# ProDoc_Schematic_Edge_Nexus_2026-03-18.net
KiCad netlist of a schematic drawn in EasyEDA Pro
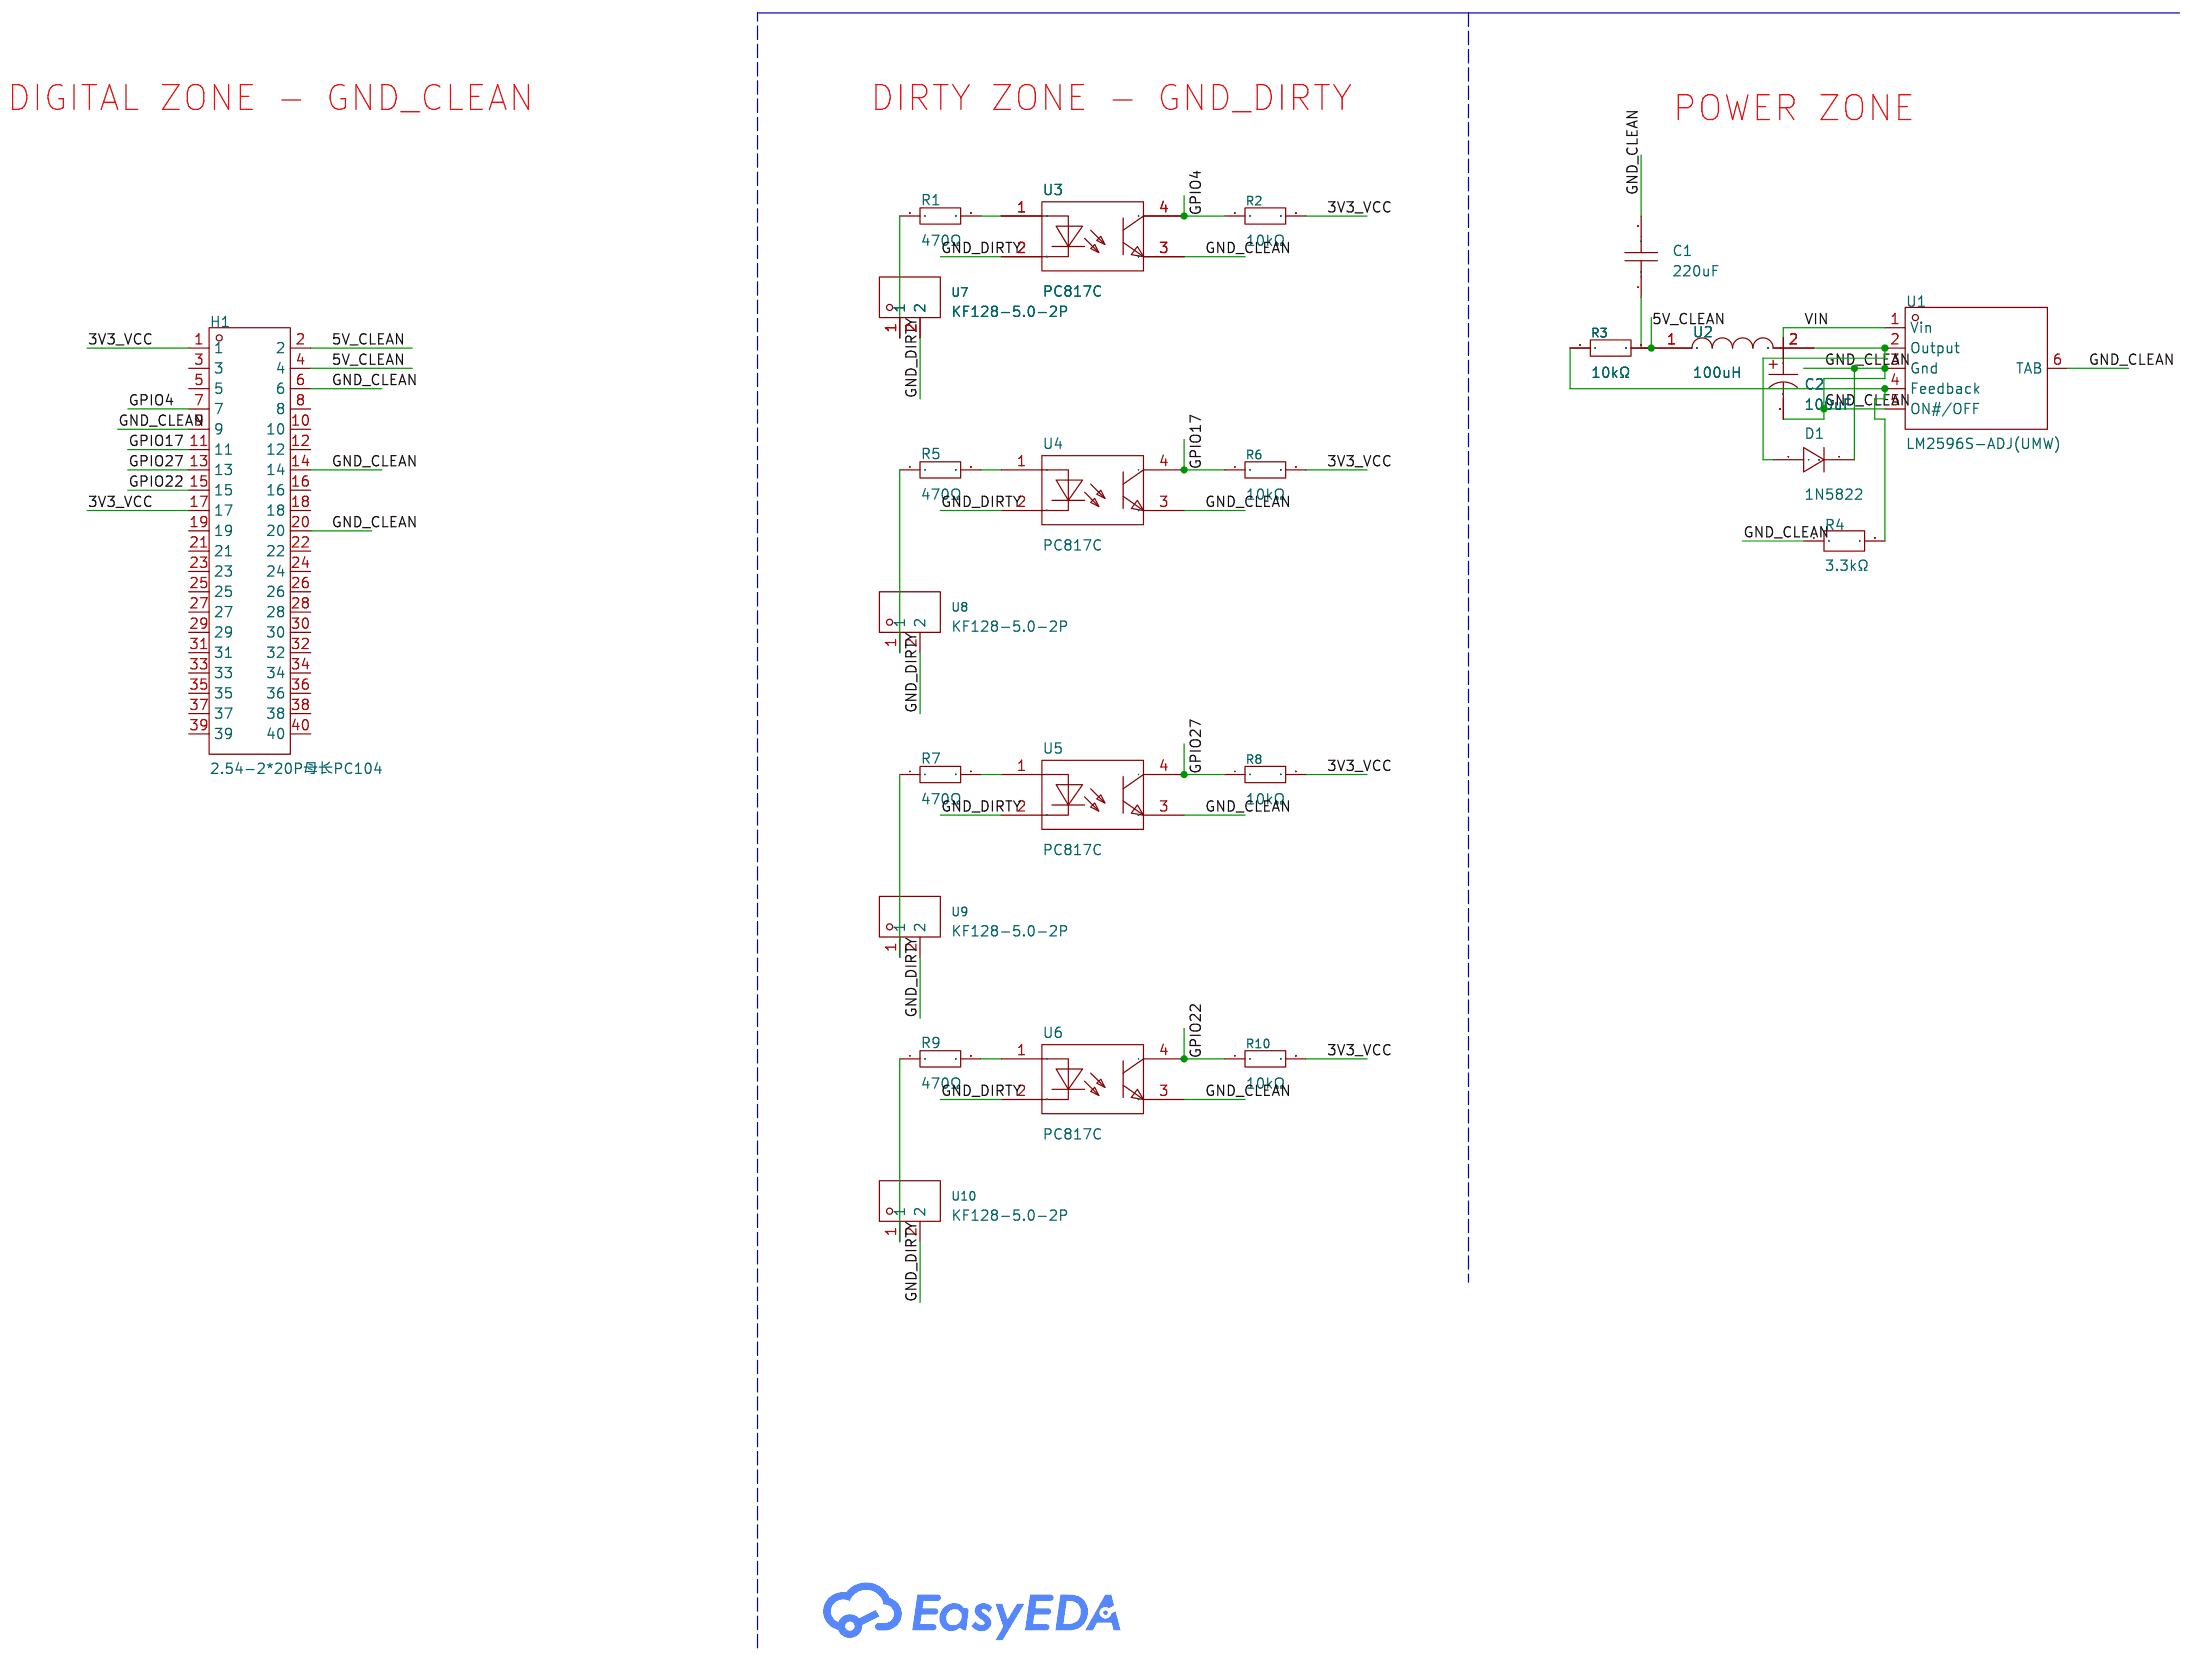
[diagram p0: schematic sheet]

(export (version "E")
  (design (tool "Eeschema 10.0.6"))
  (components
    (comp (ref "C1")
      (value "220uF")
      (footprint "easyedapro:C1210")
      (description "Capacitance:220uF Tolerance:±20% Tolerance:±20% Voltage Rating:6.3V Temperature Coefficient:X5R")
      (fields
        (field (name "Manufacturer Part") "CL32A227MQVNNNE")
        (field (name "Manufacturer") "SAMSUNG(三星)")
      )
      (libsource (lib "easyedapro") (part "CL32A227MQVNNNE"))
    )
    (comp (ref "C2")
      (value "100uF")
      (footprint "easyedapro:CAP-TH_BD8.0-P3.50-D0.6-FD-H10.0")
      (fields (field (name "Manufacturer Part") "100uF35V8x11GF") (field (name "Manufacturer") "Econd(米朗电子)"))
      (libsource (lib "easyedapro") (part "100UF35V8X11GF"))
    )
    (comp (ref "D1")
      (value "1N5822")
      (footprint "easyedapro:DO-201AD_BD5.3-L8.4-P12.50-D1.4-RD")
      (fields (field (name "Manufacturer") "LRC(乐山无线电)"))
      (libsource (lib "easyedapro") (part "1N5822_C82806"))
    )
    (comp (ref "H1")
      (value "2.54-2*20P母长PC104")
      (footprint "easyedapro:HDR-TH_40P-P2.54-V-F-R2-C20-S2.54-2")
      (fields (field (name "Manufacturer") "BOOMELE(博穆精密)"))
      (libsource (lib "easyedapro") (part "2.54mm 2*20P"))
    )
    (comp (ref "R1")
      (value "470Ω")
      (footprint "easyedapro:R0402")
      (fields (field (name "Manufacturer Part") "RC0402JR-07470RL") (field (name "Manufacturer") "YAGEO(国巨)"))
      (libsource (lib "easyedapro") (part "RC0402JR-07470RL"))
    )
    (comp (ref "R2")
      (value "10kΩ")
      (footprint "easyedapro:R0402")
      (fields
        (field (name "Manufacturer Part") "TR0402D10K0Q1025Z")
        (field (name "Manufacturer") "EVER OHMS(天二科技)")
      )
      (libsource (lib "easyedapro") (part "TR0402D10KQ1025"))
    )
    (comp (ref "R3")
      (value "10kΩ")
      (footprint "easyedapro:R0402")
      (fields
        (field (name "Manufacturer Part") "TR0402D10K0Q1025Z")
        (field (name "Manufacturer") "EVER OHMS(天二科技)")
      )
      (libsource (lib "easyedapro") (part "TR0402D10KQ1025"))
    )
    (comp (ref "R4")
      (value "3.3kΩ")
      (footprint "easyedapro:RES-TH_BD4.5-L11.5-P15.50-D0.8")
      (fields (field (name "Manufacturer Part") "MF1W-3.3KΩ±1%T") (field (name "Manufacturer") "华星机电"))
      (libsource (lib "easyedapro") (part "MF1W-3.3KΩ±1%T"))
    )
    (comp (ref "R5")
      (value "470Ω")
      (footprint "easyedapro:R0402")
      (fields (field (name "Manufacturer Part") "RC0402JR-07470RL") (field (name "Manufacturer") "YAGEO(国巨)"))
      (libsource (lib "easyedapro") (part "RC0402JR-07470RL"))
    )
    (comp (ref "R6")
      (value "10kΩ")
      (footprint "easyedapro:R0402")
      (fields
        (field (name "Manufacturer Part") "TR0402D10K0Q1025Z")
        (field (name "Manufacturer") "EVER OHMS(天二科技)")
      )
      (libsource (lib "easyedapro") (part "TR0402D10KQ1025"))
    )
    (comp (ref "R7")
      (value "470Ω")
      (footprint "easyedapro:R0402")
      (fields (field (name "Manufacturer Part") "RC0402JR-07470RL") (field (name "Manufacturer") "YAGEO(国巨)"))
      (libsource (lib "easyedapro") (part "RC0402JR-07470RL"))
    )
    (comp (ref "R8")
      (value "10kΩ")
      (footprint "easyedapro:R0402")
      (fields
        (field (name "Manufacturer Part") "TR0402D10K0Q1025Z")
        (field (name "Manufacturer") "EVER OHMS(天二科技)")
      )
      (libsource (lib "easyedapro") (part "TR0402D10KQ1025"))
    )
    (comp (ref "R9")
      (value "470Ω")
      (footprint "easyedapro:R0402")
      (fields (field (name "Manufacturer Part") "RC0402JR-07470RL") (field (name "Manufacturer") "YAGEO(国巨)"))
      (libsource (lib "easyedapro") (part "RC0402JR-07470RL"))
    )
    (comp (ref "R10")
      (value "10kΩ")
      (footprint "easyedapro:R0402")
      (fields
        (field (name "Manufacturer Part") "TR0402D10K0Q1025Z")
        (field (name "Manufacturer") "EVER OHMS(天二科技)")
      )
      (libsource (lib "easyedapro") (part "TR0402D10KQ1025"))
    )
    (comp (ref "U1")
      (value "LM2596S-ADJ(UMW)")
      (footprint "easyedapro:TO-263-5_L10.2-W8.9-P1.70-BR")
      (fields (field (name "Manufacturer") "UMW(友台半导体)"))
      (libsource (lib "easyedapro") (part "LM2596S-ADJ"))
    )
    (comp (ref "U2")
      (value "100uH")
      (footprint "easyedapro:IND-SMD_L12.3-W12.3")
      (fields (field (name "Manufacturer Part") "CYH127-100UH") (field (name "Manufacturer") "SHOU HAN(首韩)"))
      (libsource (lib "easyedapro") (part "CYH127-100UH"))
    )
    (comp (ref "U3")
      (value "PC817C")
      (footprint "easyedapro:OPTO-SMD-4_L4.6-W6.5-P2.54-LS10.3-TL")
      (fields (field (name "Manufacturer") "GOODWORK(固得沃克)"))
      (libsource (lib "easyedapro") (part "PC817C_C3025164"))
    )
    (comp (ref "U4")
      (value "PC817C")
      (footprint "easyedapro:OPTO-SMD-4_L4.6-W6.5-P2.54-LS10.3-TL")
      (fields (field (name "Manufacturer") "GOODWORK(固得沃克)"))
      (libsource (lib "easyedapro") (part "PC817C_C3025164"))
    )
    (comp (ref "U5")
      (value "PC817C")
      (footprint "easyedapro:OPTO-SMD-4_L4.6-W6.5-P2.54-LS10.3-TL")
      (fields (field (name "Manufacturer") "GOODWORK(固得沃克)"))
      (libsource (lib "easyedapro") (part "PC817C_C3025164"))
    )
    (comp (ref "U6")
      (value "PC817C")
      (footprint "easyedapro:OPTO-SMD-4_L4.6-W6.5-P2.54-LS10.3-TL")
      (fields (field (name "Manufacturer") "GOODWORK(固得沃克)"))
      (libsource (lib "easyedapro") (part "PC817C_C3025164"))
    )
    (comp (ref "U7")
      (value "KF128-5.0-2P")
      (footprint "easyedapro:CONN-TH_P5.00_KF128-5.0-2P")
      (fields (field (name "Manufacturer") "KEFA(科发)"))
      (libsource (lib "easyedapro") (part "KF128-5.0-2P"))
    )
    (comp (ref "U8")
      (value "KF128-5.0-2P")
      (footprint "easyedapro:CONN-TH_P5.00_KF128-5.0-2P")
      (fields (field (name "Manufacturer") "KEFA(科发)"))
      (libsource (lib "easyedapro") (part "KF128-5.0-2P"))
    )
    (comp (ref "U9")
      (value "KF128-5.0-2P")
      (footprint "easyedapro:CONN-TH_P5.00_KF128-5.0-2P")
      (fields (field (name "Manufacturer") "KEFA(科发)"))
      (libsource (lib "easyedapro") (part "KF128-5.0-2P"))
    )
    (comp (ref "U10")
      (value "KF128-5.0-2P")
      (footprint "easyedapro:CONN-TH_P5.00_KF128-5.0-2P")
      (fields (field (name "Manufacturer") "KEFA(科发)"))
      (libsource (lib "easyedapro") (part "KF128-5.0-2P"))
    )
  )
  (nets
    (net (code "1") (name "/3V3_VCC") (class "Default")
      (node (ref "H1") (pin "1") (pinfunction "1_1") (pintype "unspecified"))
      (node (ref "H1") (pin "17") (pinfunction "17_17") (pintype "unspecified"))
      (node (ref "R10") (pin "2") (pinfunction "2_2") (pintype "input"))
      (node (ref "R2") (pin "2") (pinfunction "2_2") (pintype "input"))
      (node (ref "R6") (pin "2") (pinfunction "2_2") (pintype "input"))
      (node (ref "R8") (pin "2") (pinfunction "2_2") (pintype "input"))
    )
    (net (code "2") (name "/5V_CLEAN") (class "Default")
      (node (ref "C1") (pin "1") (pinfunction "1_1") (pintype "unspecified"))
      (node (ref "H1") (pin "2") (pinfunction "2_2") (pintype "unspecified"))
      (node (ref "H1") (pin "4") (pinfunction "4_4") (pintype "unspecified"))
      (node (ref "R3") (pin "2") (pinfunction "2_2") (pintype "input"))
      (node (ref "U2") (pin "1") (pinfunction "1_1") (pintype "unspecified"))
    )
    (net (code "3") (name "/GND_CLEAN") (class "Default")
      (node (ref "C1") (pin "2") (pinfunction "2_2") (pintype "unspecified"))
      (node (ref "C2") (pin "2") (pinfunction "2_2") (pintype "input"))
      (node (ref "D1") (pin "1") (pinfunction "C_1") (pintype "unspecified"))
      (node (ref "H1") (pin "14") (pinfunction "14_14") (pintype "unspecified"))
      (node (ref "H1") (pin "20") (pinfunction "20_20") (pintype "unspecified"))
      (node (ref "H1") (pin "6") (pinfunction "6_6") (pintype "unspecified"))
      (node (ref "H1") (pin "9") (pinfunction "9_9") (pintype "unspecified"))
      (node (ref "R4") (pin "1") (pinfunction "1_1") (pintype "unspecified"))
      (node (ref "U1") (pin "3") (pinfunction "Gnd_3") (pintype "unspecified"))
      (node (ref "U1") (pin "5") (pinfunction "ON#/OFF_5") (pintype "unspecified"))
      (node (ref "U1") (pin "6") (pinfunction "TAB_6") (pintype "unspecified"))
      (node (ref "U3") (pin "3") (pinfunction "3_3") (pintype "unspecified"))
      (node (ref "U4") (pin "3") (pinfunction "3_3") (pintype "unspecified"))
      (node (ref "U5") (pin "3") (pinfunction "3_3") (pintype "unspecified"))
      (node (ref "U6") (pin "3") (pinfunction "3_3") (pintype "unspecified"))
    )
    (net (code "4") (name "/GND_DIRTY") (class "Default")
      (node (ref "U10") (pin "2") (pinfunction "2_2") (pintype "input"))
      (node (ref "U3") (pin "2") (pinfunction "2_2") (pintype "unspecified"))
      (node (ref "U4") (pin "2") (pinfunction "2_2") (pintype "unspecified"))
      (node (ref "U5") (pin "2") (pinfunction "2_2") (pintype "unspecified"))
      (node (ref "U6") (pin "2") (pinfunction "2_2") (pintype "unspecified"))
      (node (ref "U7") (pin "2") (pinfunction "2_2") (pintype "input"))
      (node (ref "U8") (pin "2") (pinfunction "2_2") (pintype "input"))
      (node (ref "U9") (pin "2") (pinfunction "2_2") (pintype "input"))
    )
    (net (code "5") (name "/GPIO4") (class "Default")
      (node (ref "H1") (pin "7") (pinfunction "7_7") (pintype "unspecified"))
      (node (ref "R2") (pin "1") (pinfunction "1_1") (pintype "input"))
      (node (ref "U3") (pin "4") (pinfunction "4_4") (pintype "unspecified"))
    )
    (net (code "6") (name "/GPIO17") (class "Default")
      (node (ref "H1") (pin "11") (pinfunction "11_11") (pintype "unspecified"))
      (node (ref "R6") (pin "1") (pinfunction "1_1") (pintype "input"))
      (node (ref "U4") (pin "4") (pinfunction "4_4") (pintype "unspecified"))
    )
    (net (code "7") (name "/GPIO22") (class "Default")
      (node (ref "H1") (pin "15") (pinfunction "15_15") (pintype "unspecified"))
      (node (ref "R10") (pin "1") (pinfunction "1_1") (pintype "input"))
      (node (ref "U6") (pin "4") (pinfunction "4_4") (pintype "unspecified"))
    )
    (net (code "8") (name "/GPIO27") (class "Default")
      (node (ref "H1") (pin "13") (pinfunction "13_13") (pintype "unspecified"))
      (node (ref "R8") (pin "1") (pinfunction "1_1") (pintype "input"))
      (node (ref "U5") (pin "4") (pinfunction "4_4") (pintype "unspecified"))
    )
    (net (code "9") (name "/VIN") (class "Default")
      (node (ref "C2") (pin "1") (pinfunction "1_1") (pintype "input"))
      (node (ref "U1") (pin "1") (pinfunction "Vin_1") (pintype "unspecified"))
    )
    (net (code "10") (name "Net-(D1-A)") (class "Default")
      (node (ref "D1") (pin "2") (pinfunction "A_2") (pintype "unspecified"))
      (node (ref "U1") (pin "2") (pinfunction "Output_2") (pintype "unspecified"))
      (node (ref "U2") (pin "2") (pinfunction "2_2") (pintype "unspecified"))
    )
    (net (code "11") (name "Net-(R1-Pad1)") (class "Default")
      (node (ref "R1") (pin "1") (pinfunction "1_1") (pintype "input"))
      (node (ref "U7") (pin "1") (pinfunction "1_1") (pintype "input"))
    )
    (net (code "12") (name "Net-(R1-Pad2)") (class "Default")
      (node (ref "R1") (pin "2") (pinfunction "2_2") (pintype "input"))
      (node (ref "U3") (pin "1") (pinfunction "1_1") (pintype "unspecified"))
    )
    (net (code "13") (name "Net-(R5-Pad1)") (class "Default")
      (node (ref "R5") (pin "1") (pinfunction "1_1") (pintype "input"))
      (node (ref "U8") (pin "1") (pinfunction "1_1") (pintype "input"))
    )
    (net (code "14") (name "Net-(R5-Pad2)") (class "Default")
      (node (ref "R5") (pin "2") (pinfunction "2_2") (pintype "input"))
      (node (ref "U4") (pin "1") (pinfunction "1_1") (pintype "unspecified"))
    )
    (net (code "15") (name "Net-(R7-Pad1)") (class "Default")
      (node (ref "R7") (pin "1") (pinfunction "1_1") (pintype "input"))
      (node (ref "U9") (pin "1") (pinfunction "1_1") (pintype "input"))
    )
    (net (code "16") (name "Net-(R7-Pad2)") (class "Default")
      (node (ref "R7") (pin "2") (pinfunction "2_2") (pintype "input"))
      (node (ref "U5") (pin "1") (pinfunction "1_1") (pintype "unspecified"))
    )
    (net (code "17") (name "Net-(R9-Pad1)") (class "Default")
      (node (ref "R9") (pin "1") (pinfunction "1_1") (pintype "input"))
      (node (ref "U10") (pin "1") (pinfunction "1_1") (pintype "input"))
    )
    (net (code "18") (name "Net-(R9-Pad2)") (class "Default")
      (node (ref "R9") (pin "2") (pinfunction "2_2") (pintype "input"))
      (node (ref "U6") (pin "1") (pinfunction "1_1") (pintype "unspecified"))
    )
    (net (code "19") (name "Net-(U1-Feedback)") (class "Default")
      (node (ref "R3") (pin "1") (pinfunction "1_1") (pintype "input"))
      (node (ref "R4") (pin "2") (pinfunction "2_2") (pintype "unspecified"))
      (node (ref "U1") (pin "4") (pinfunction "Feedback_4") (pintype "unspecified"))
    )
    (net (code "20") (name "unconnected-(H1-Pad3)") (class "Default")
      (node (ref "H1") (pin "3") (pinfunction "3_3") (pintype "unspecified"))
    )
    (net (code "21") (name "unconnected-(H1-Pad5)") (class "Default")
      (node (ref "H1") (pin "5") (pinfunction "5_5") (pintype "unspecified"))
    )
    (net (code "22") (name "unconnected-(H1-Pad8)") (class "Default")
      (node (ref "H1") (pin "8") (pinfunction "8_8") (pintype "unspecified"))
    )
    (net (code "23") (name "unconnected-(H1-Pad10)") (class "Default")
      (node (ref "H1") (pin "10") (pinfunction "10_10") (pintype "unspecified"))
    )
    (net (code "24") (name "unconnected-(H1-Pad12)") (class "Default")
      (node (ref "H1") (pin "12") (pinfunction "12_12") (pintype "unspecified"))
    )
    (net (code "25") (name "unconnected-(H1-Pad16)") (class "Default")
      (node (ref "H1") (pin "16") (pinfunction "16_16") (pintype "unspecified"))
    )
    (net (code "26") (name "unconnected-(H1-Pad18)") (class "Default")
      (node (ref "H1") (pin "18") (pinfunction "18_18") (pintype "unspecified"))
    )
    (net (code "27") (name "unconnected-(H1-Pad19)") (class "Default")
      (node (ref "H1") (pin "19") (pinfunction "19_19") (pintype "unspecified"))
    )
    (net (code "28") (name "unconnected-(H1-Pad21)") (class "Default")
      (node (ref "H1") (pin "21") (pinfunction "21_21") (pintype "unspecified"))
    )
    (net (code "29") (name "unconnected-(H1-Pad22)") (class "Default")
      (node (ref "H1") (pin "22") (pinfunction "22_22") (pintype "unspecified"))
    )
    (net (code "30") (name "unconnected-(H1-Pad23)") (class "Default")
      (node (ref "H1") (pin "23") (pinfunction "23_23") (pintype "unspecified"))
    )
    (net (code "31") (name "unconnected-(H1-Pad24)") (class "Default")
      (node (ref "H1") (pin "24") (pinfunction "24_24") (pintype "unspecified"))
    )
    (net (code "32") (name "unconnected-(H1-Pad25)") (class "Default")
      (node (ref "H1") (pin "25") (pinfunction "25_25") (pintype "unspecified"))
    )
    (net (code "33") (name "unconnected-(H1-Pad26)") (class "Default")
      (node (ref "H1") (pin "26") (pinfunction "26_26") (pintype "unspecified"))
    )
    (net (code "34") (name "unconnected-(H1-Pad27)") (class "Default")
      (node (ref "H1") (pin "27") (pinfunction "27_27") (pintype "unspecified"))
    )
    (net (code "35") (name "unconnected-(H1-Pad28)") (class "Default")
      (node (ref "H1") (pin "28") (pinfunction "28_28") (pintype "unspecified"))
    )
    (net (code "36") (name "unconnected-(H1-Pad29)") (class "Default")
      (node (ref "H1") (pin "29") (pinfunction "29_29") (pintype "unspecified"))
    )
    (net (code "37") (name "unconnected-(H1-Pad30)") (class "Default")
      (node (ref "H1") (pin "30") (pinfunction "30_30") (pintype "unspecified"))
    )
    (net (code "38") (name "unconnected-(H1-Pad31)") (class "Default")
      (node (ref "H1") (pin "31") (pinfunction "31_31") (pintype "unspecified"))
    )
    (net (code "39") (name "unconnected-(H1-Pad32)") (class "Default")
      (node (ref "H1") (pin "32") (pinfunction "32_32") (pintype "unspecified"))
    )
    (net (code "40") (name "unconnected-(H1-Pad33)") (class "Default")
      (node (ref "H1") (pin "33") (pinfunction "33_33") (pintype "unspecified"))
    )
    (net (code "41") (name "unconnected-(H1-Pad34)") (class "Default")
      (node (ref "H1") (pin "34") (pinfunction "34_34") (pintype "unspecified"))
    )
    (net (code "42") (name "unconnected-(H1-Pad35)") (class "Default")
      (node (ref "H1") (pin "35") (pinfunction "35_35") (pintype "unspecified"))
    )
    (net (code "43") (name "unconnected-(H1-Pad36)") (class "Default")
      (node (ref "H1") (pin "36") (pinfunction "36_36") (pintype "unspecified"))
    )
    (net (code "44") (name "unconnected-(H1-Pad37)") (class "Default")
      (node (ref "H1") (pin "37") (pinfunction "37_37") (pintype "unspecified"))
    )
    (net (code "45") (name "unconnected-(H1-Pad38)") (class "Default")
      (node (ref "H1") (pin "38") (pinfunction "38_38") (pintype "unspecified"))
    )
    (net (code "46") (name "unconnected-(H1-Pad39)") (class "Default")
      (node (ref "H1") (pin "39") (pinfunction "39_39") (pintype "unspecified"))
    )
    (net (code "47") (name "unconnected-(H1-Pad40)") (class "Default")
      (node (ref "H1") (pin "40") (pinfunction "40_40") (pintype "unspecified"))
    )
  )
)
